# Overview.net
KiCad netlist of a schematic drawn in Altium Designer
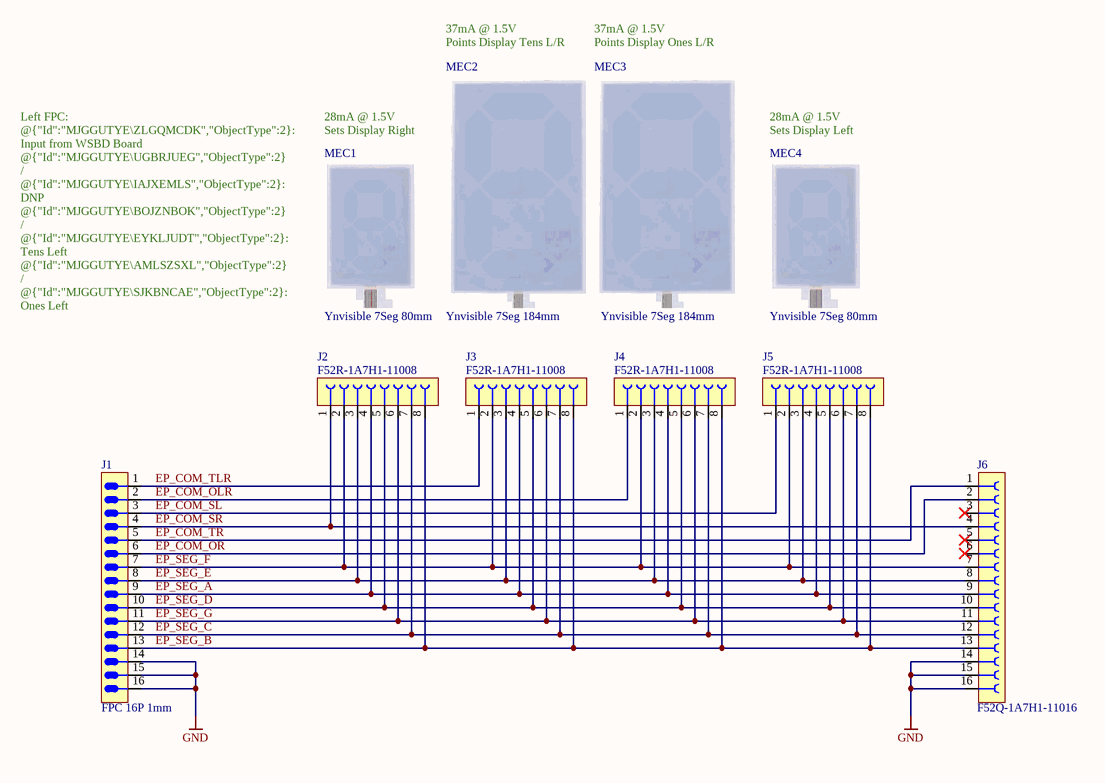
[diagram p0: Overview.SchDoc]

(export (version "E")
  (design (tool "Eeschema 10.0.6"))
  (components
    (comp (ref "J1")
      (value "FPC 16P 1mm")
      (footprint "6pin FPC 1mm")
      (description "CONN FPC 16POS 1mm")
      (libsource (lib "ETHZ Vault") (part "CON 16x1 Male"))
    )
    (comp (ref "J2")
      (value "F52R-1A7H1-11008")
      (footprint "F52R-1A7H1-11008")
      (description "CONN FPC TOP 8POS 1mm")
      (fields (field (name "MANUFACTURER") "Amphenol ICC (FCI)"))
      (libsource (lib "ETHZ Vault") (part "CON 8x1 Female"))
    )
    (comp (ref "J3")
      (value "F52R-1A7H1-11008")
      (footprint "F52R-1A7H1-11008")
      (description "CONN FPC TOP 8POS 1mm")
      (fields (field (name "MANUFACTURER") "Amphenol ICC (FCI)"))
      (libsource (lib "ETHZ Vault") (part "CON 8x1 Female"))
    )
    (comp (ref "J4")
      (value "F52R-1A7H1-11008")
      (footprint "F52R-1A7H1-11008")
      (description "CONN FPC TOP 8POS 1mm")
      (fields (field (name "MANUFACTURER") "Amphenol ICC (FCI)"))
      (libsource (lib "ETHZ Vault") (part "CON 8x1 Female"))
    )
    (comp (ref "J5")
      (value "F52R-1A7H1-11008")
      (footprint "F52R-1A7H1-11008")
      (description "CONN FPC TOP 8POS 1mm")
      (fields (field (name "MANUFACTURER") "Amphenol ICC (FCI)"))
      (libsource (lib "ETHZ Vault") (part "CON 8x1 Female"))
    )
    (comp (ref "J6")
      (value "F52Q-1A7H1-11016")
      (footprint "F52Q-1A7H1-11016")
      (description "CONN FPC TOP 16POS 1mm")
      (fields (field (name "MANUFACTURER") "Amphenol ICC (FCI)"))
      (libsource (lib "ETHZ Vault") (part "CON 16x1 Female"))
    )
    (comp (ref "MEC1")
      (value "Ynvisible 7Seg 80mm")
      (description "EMECH SINGLE EPAPER 7SEG 80MM")
      (fields
        (field (name "MANUFACTURER") "Ynvisible")
        (field (name "MANUFACTURER PART NUMBER") "LARGE E-PAPER DISPLAY – SINGLE DIGIT 80MM")
      )
      (libsource (lib "ETHZ Vault") (part "LARGE E-PAPER DISPLAY – SINGLE DIGIT 184MM"))
    )
    (comp (ref "MEC2")
      (value "Ynvisible 7Seg 184mm")
      (description "EMECH SINGLE EPAPER 7SEG 184MM")
      (fields
        (field (name "MANUFACTURER") "Ynvisible")
        (field (name "MANUFACTURER PART NUMBER") "LARGE E-PAPER DISPLAY – SINGLE DIGIT 184MM")
      )
      (libsource (lib "ETHZ Vault") (part "LARGE E-PAPER DISPLAY – SINGLE DIGIT 184MM"))
    )
    (comp (ref "MEC3")
      (value "Ynvisible 7Seg 184mm")
      (description "EMECH SINGLE EPAPER 7SEG 184MM")
      (fields
        (field (name "MANUFACTURER") "Ynvisible")
        (field (name "MANUFACTURER PART NUMBER") "LARGE E-PAPER DISPLAY – SINGLE DIGIT 184MM")
      )
      (libsource (lib "ETHZ Vault") (part "LARGE E-PAPER DISPLAY – SINGLE DIGIT 184MM"))
    )
    (comp (ref "MEC4")
      (value "Ynvisible 7Seg 80mm")
      (description "EMECH SINGLE EPAPER 7SEG 80MM")
      (fields
        (field (name "MANUFACTURER") "Ynvisible")
        (field (name "MANUFACTURER PART NUMBER") "LARGE E-PAPER DISPLAY – SINGLE DIGIT 80MM")
      )
      (libsource (lib "ETHZ Vault") (part "LARGE E-PAPER DISPLAY – SINGLE DIGIT 184MM"))
    )
  )
  (nets
    (net (code "1") (name "/EP_COM_OLR") (class "Default")
      (node (ref "J1") (pin "2") (pinfunction "2_2") (pintype "passive"))
      (node (ref "J4") (pin "1") (pinfunction "1_1") (pintype "passive"))
    )
    (net (code "2") (name "/EP_COM_OR") (class "Default")
      (node (ref "J1") (pin "6") (pinfunction "6_6") (pintype "passive"))
      (node (ref "J6") (pin "2") (pinfunction "2_2") (pintype "passive"))
    )
    (net (code "3") (name "/EP_COM_SL") (class "Default")
      (node (ref "J1") (pin "3") (pinfunction "3_3") (pintype "passive"))
      (node (ref "J5") (pin "1") (pinfunction "1_1") (pintype "passive"))
    )
    (net (code "4") (name "/EP_COM_SR") (class "Default")
      (node (ref "J1") (pin "4") (pinfunction "4_4") (pintype "passive"))
      (node (ref "J2") (pin "1") (pinfunction "1_1") (pintype "passive"))
      (node (ref "J6") (pin "4") (pinfunction "4_4") (pintype "passive"))
    )
    (net (code "5") (name "/EP_COM_TLR") (class "Default")
      (node (ref "J1") (pin "1") (pinfunction "1_1") (pintype "passive"))
      (node (ref "J3") (pin "1") (pinfunction "1_1") (pintype "passive"))
    )
    (net (code "6") (name "/EP_COM_TR") (class "Default")
      (node (ref "J1") (pin "5") (pinfunction "5_5") (pintype "passive"))
      (node (ref "J6") (pin "1") (pinfunction "1_1") (pintype "passive"))
    )
    (net (code "7") (name "/EP_SEG_A") (class "Default")
      (node (ref "J1") (pin "9") (pinfunction "9_9") (pintype "passive"))
      (node (ref "J2") (pin "4") (pinfunction "4_4") (pintype "passive"))
      (node (ref "J3") (pin "4") (pinfunction "4_4") (pintype "passive"))
      (node (ref "J4") (pin "4") (pinfunction "4_4") (pintype "passive"))
      (node (ref "J5") (pin "4") (pinfunction "4_4") (pintype "passive"))
      (node (ref "J6") (pin "9") (pinfunction "9_9") (pintype "passive"))
    )
    (net (code "8") (name "/EP_SEG_B") (class "Default")
      (node (ref "J1") (pin "13") (pinfunction "13_13") (pintype "passive"))
      (node (ref "J2") (pin "8") (pinfunction "8_8") (pintype "passive"))
      (node (ref "J3") (pin "8") (pinfunction "8_8") (pintype "passive"))
      (node (ref "J4") (pin "8") (pinfunction "8_8") (pintype "passive"))
      (node (ref "J5") (pin "8") (pinfunction "8_8") (pintype "passive"))
      (node (ref "J6") (pin "13") (pinfunction "13_13") (pintype "passive"))
    )
    (net (code "9") (name "/EP_SEG_C") (class "Default")
      (node (ref "J1") (pin "12") (pinfunction "12_12") (pintype "passive"))
      (node (ref "J2") (pin "7") (pinfunction "7_7") (pintype "passive"))
      (node (ref "J3") (pin "7") (pinfunction "7_7") (pintype "passive"))
      (node (ref "J4") (pin "7") (pinfunction "7_7") (pintype "passive"))
      (node (ref "J5") (pin "7") (pinfunction "7_7") (pintype "passive"))
      (node (ref "J6") (pin "12") (pinfunction "12_12") (pintype "passive"))
    )
    (net (code "10") (name "/EP_SEG_D") (class "Default")
      (node (ref "J1") (pin "10") (pinfunction "10_10") (pintype "passive"))
      (node (ref "J2") (pin "5") (pinfunction "5_5") (pintype "passive"))
      (node (ref "J3") (pin "5") (pinfunction "5_5") (pintype "passive"))
      (node (ref "J4") (pin "5") (pinfunction "5_5") (pintype "passive"))
      (node (ref "J5") (pin "5") (pinfunction "5_5") (pintype "passive"))
      (node (ref "J6") (pin "10") (pinfunction "10_10") (pintype "passive"))
    )
    (net (code "11") (name "/EP_SEG_E") (class "Default")
      (node (ref "J1") (pin "8") (pinfunction "8_8") (pintype "passive"))
      (node (ref "J2") (pin "3") (pinfunction "3_3") (pintype "passive"))
      (node (ref "J3") (pin "3") (pinfunction "3_3") (pintype "passive"))
      (node (ref "J4") (pin "3") (pinfunction "3_3") (pintype "passive"))
      (node (ref "J5") (pin "3") (pinfunction "3_3") (pintype "passive"))
      (node (ref "J6") (pin "8") (pinfunction "8_8") (pintype "passive"))
    )
    (net (code "12") (name "/EP_SEG_F") (class "Default")
      (node (ref "J1") (pin "7") (pinfunction "7_7") (pintype "passive"))
      (node (ref "J2") (pin "2") (pinfunction "2_2") (pintype "passive"))
      (node (ref "J3") (pin "2") (pinfunction "2_2") (pintype "passive"))
      (node (ref "J4") (pin "2") (pinfunction "2_2") (pintype "passive"))
      (node (ref "J5") (pin "2") (pinfunction "2_2") (pintype "passive"))
      (node (ref "J6") (pin "7") (pinfunction "7_7") (pintype "passive"))
    )
    (net (code "13") (name "/EP_SEG_G") (class "Default")
      (node (ref "J1") (pin "11") (pinfunction "11_11") (pintype "passive"))
      (node (ref "J2") (pin "6") (pinfunction "6_6") (pintype "passive"))
      (node (ref "J3") (pin "6") (pinfunction "6_6") (pintype "passive"))
      (node (ref "J4") (pin "6") (pinfunction "6_6") (pintype "passive"))
      (node (ref "J5") (pin "6") (pinfunction "6_6") (pintype "passive"))
      (node (ref "J6") (pin "11") (pinfunction "11_11") (pintype "passive"))
    )
    (net (code "14") (name "GND") (class "Default")
      (node (ref "J1") (pin "14") (pinfunction "14_14") (pintype "passive"))
      (node (ref "J1") (pin "15") (pinfunction "15_15") (pintype "passive"))
      (node (ref "J1") (pin "16") (pinfunction "16_16") (pintype "passive"))
      (node (ref "J6") (pin "14") (pinfunction "14_14") (pintype "passive"))
      (node (ref "J6") (pin "15") (pinfunction "15_15") (pintype "passive"))
      (node (ref "J6") (pin "16") (pinfunction "16_16") (pintype "passive"))
    )
    (net (code "15") (name "unconnected-(J6-Pad3)") (class "Default")
      (node (ref "J6") (pin "3") (pinfunction "3_3") (pintype "passive+no_connect"))
    )
    (net (code "16") (name "unconnected-(J6-Pad5)") (class "Default")
      (node (ref "J6") (pin "5") (pinfunction "5_5") (pintype "passive+no_connect"))
    )
    (net (code "17") (name "unconnected-(J6-Pad6)") (class "Default")
      (node (ref "J6") (pin "6") (pinfunction "6_6") (pintype "passive+no_connect"))
    )
  )
)
